# cloud_humidity_sensor.net
KiCad netlist of a schematic drawn in EAGLE
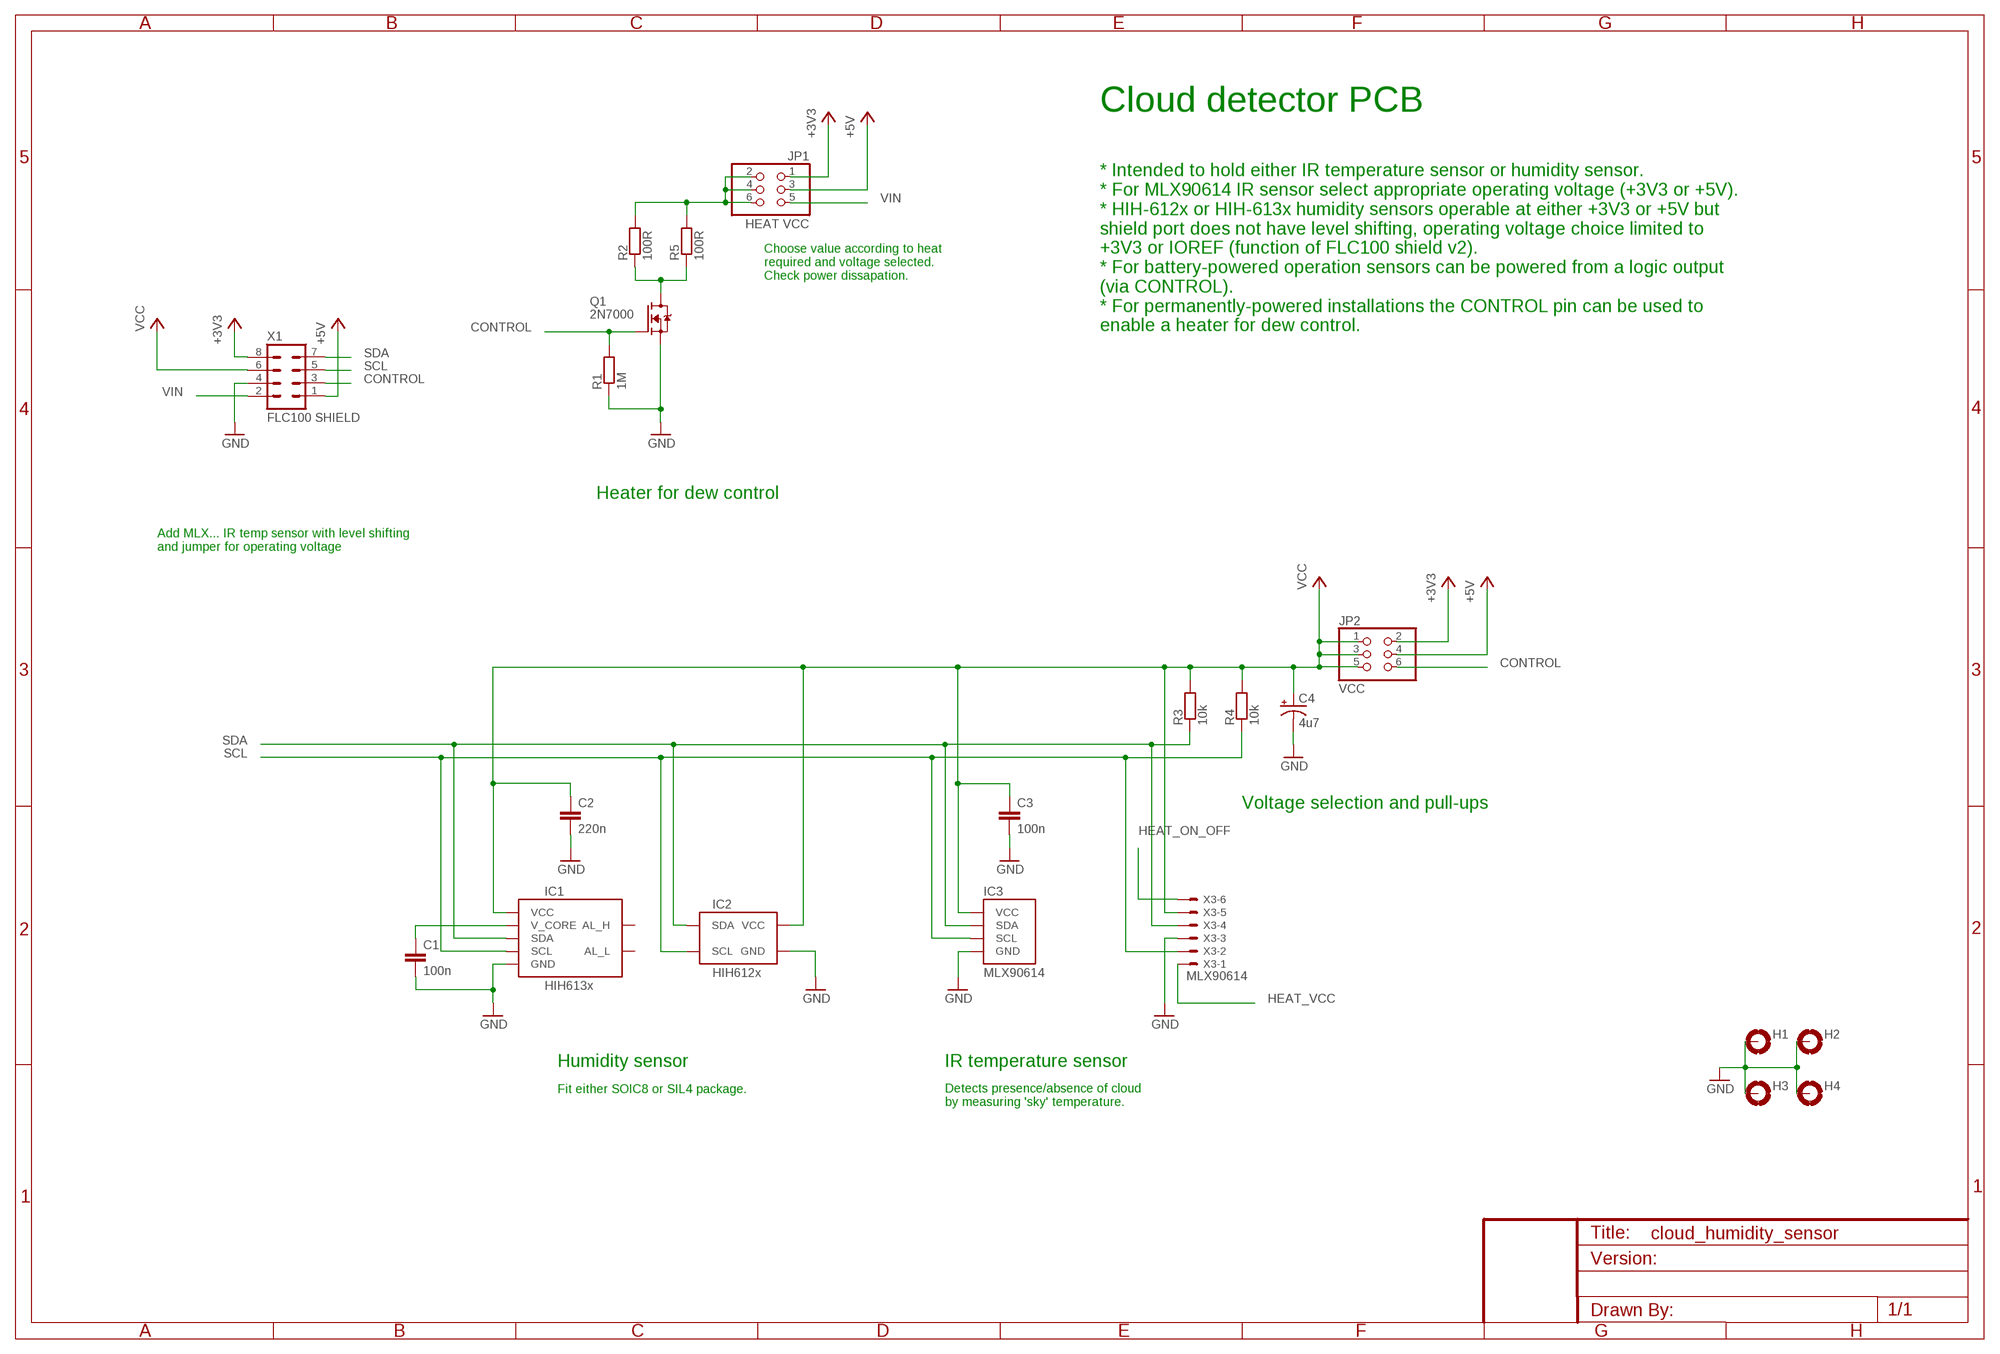
[diagram p0: schematic, sheet 1]

(export (version "E")
  (design (tool "Eeschema 10.0.6"))
  (components
    (comp (ref "C1")
      (value "100n")
      (footprint "eagle-import:CAP-PTH-SMALL")
      (libsource (lib "eagle-import") (part "CAPPTH"))
    )
    (comp (ref "C2")
      (value "220n")
      (footprint "eagle-import:CAP-PTH-SMALL")
      (libsource (lib "eagle-import") (part "CAPPTH"))
    )
    (comp (ref "C3")
      (value "100n")
      (footprint "eagle-import:CAP-PTH-SMALL")
      (libsource (lib "eagle-import") (part "CAPPTH"))
    )
    (comp (ref "C4")
      (value "4u7")
      (footprint "eagle-import:CPOL-RADIAL-10UF-25V")
      (libsource (lib "eagle-import") (part "CAP_POLPTH2"))
    )
    (comp (ref "H1")
      (value "MOUNT-PAD-ROUND3.0")
      (footprint "eagle-import:3,0-PAD")
      (libsource (lib "eagle-import") (part "MOUNT-PAD-ROUND3.0"))
    )
    (comp (ref "H2")
      (value "MOUNT-PAD-ROUND3.0")
      (footprint "eagle-import:3,0-PAD")
      (libsource (lib "eagle-import") (part "MOUNT-PAD-ROUND3.0"))
    )
    (comp (ref "H3")
      (value "MOUNT-PAD-ROUND3.0")
      (footprint "eagle-import:3,0-PAD")
      (libsource (lib "eagle-import") (part "MOUNT-PAD-ROUND3.0"))
    )
    (comp (ref "H4")
      (value "MOUNT-PAD-ROUND3.0")
      (footprint "eagle-import:3,0-PAD")
      (libsource (lib "eagle-import") (part "MOUNT-PAD-ROUND3.0"))
    )
    (comp (ref "IC1")
      (value "HIH613x")
      (footprint "eagle-import:SO08")
      (libsource (lib "eagle-import") (part "HONEYWELL-HIH613XSOIC8"))
    )
    (comp (ref "IC2")
      (value "HIH612x")
      (footprint "eagle-import:SIL04")
      (libsource (lib "eagle-import") (part "HONEYWELL-HIH612X"))
    )
    (comp (ref "IC3")
      (value "MLX90614")
      (footprint "eagle-import:TO39-4")
      (libsource (lib "eagle-import") (part "MLX90614TO-39"))
    )
    (comp (ref "JP1")
      (value "HEAT VCC")
      (footprint "eagle-import:2X03")
      (libsource (lib "eagle-import") (part "PINHD-2X3"))
    )
    (comp (ref "JP2")
      (value "VCC")
      (footprint "eagle-import:2X03")
      (libsource (lib "eagle-import") (part "PINHD-2X3"))
    )
    (comp (ref "Q1")
      (value "2N7000")
      (footprint "eagle-import:TO-92")
      (libsource (lib "eagle-import") (part "2N7000"))
    )
    (comp (ref "R1")
      (value "1M")
      (footprint "eagle-import:RES-AXIAL-0.4")
      (libsource (lib "eagle-import") (part "RESISTOR"))
    )
    (comp (ref "R2")
      (value "100R")
      (footprint "eagle-import:RES-AXIAL-0.4")
      (libsource (lib "eagle-import") (part "RESISTOR"))
    )
    (comp (ref "R3")
      (value "10k")
      (footprint "eagle-import:RES-AXIAL-0.4")
      (libsource (lib "eagle-import") (part "RESISTOR"))
    )
    (comp (ref "R4")
      (value "10k")
      (footprint "eagle-import:RES-AXIAL-0.4")
      (libsource (lib "eagle-import") (part "RESISTOR"))
    )
    (comp (ref "R5")
      (value "100R")
      (footprint "eagle-import:RES-AXIAL-0.4")
      (libsource (lib "eagle-import") (part "RESISTOR"))
    )
    (comp (ref "X1")
      (value "FLC100 SHIELD")
      (footprint "eagle-import:ML8")
      (libsource (lib "eagle-import") (part "ML8"))
    )
    (comp (ref "X3")
      (value "MLX90614")
      (footprint "eagle-import:22-23-2061")
      (fields (field (name "MF") "MOLEX") (field (name "MPN") "22-23-2061"))
      (libsource (lib "eagle-import") (part "22-23-2061"))
    )
  )
  (nets
    (net (code "1") (name "+3V3") (class "Default")
      (node (ref "JP1") (pin "1") (pinfunction "1_1") (pintype "passive"))
      (node (ref "JP2") (pin "2") (pinfunction "2_2") (pintype "passive"))
      (node (ref "X1") (pin "8") (pinfunction "8_8") (pintype "passive"))
    )
    (net (code "2") (name "+5V") (class "Default")
      (node (ref "JP1") (pin "3") (pinfunction "3_3") (pintype "passive"))
      (node (ref "JP2") (pin "4") (pinfunction "4_4") (pintype "passive"))
      (node (ref "X1") (pin "1") (pinfunction "1_1") (pintype "passive"))
    )
    (net (code "3") (name "/CONTROL") (class "Default")
      (node (ref "JP2") (pin "6") (pinfunction "6_6") (pintype "passive"))
      (node (ref "Q1") (pin "2") (pinfunction "G_2") (pintype "passive"))
      (node (ref "R1") (pin "P$2") (pinfunction "2_P$2") (pintype "passive"))
      (node (ref "X1") (pin "3") (pinfunction "3_3") (pintype "passive"))
    )
    (net (code "4") (name "/HEAT_ON_OFF") (class "Default")
      (node (ref "Q1") (pin "3") (pinfunction "D_3") (pintype "passive"))
      (node (ref "R2") (pin "P$1") (pinfunction "1_P$1") (pintype "passive"))
      (node (ref "R5") (pin "P$1") (pinfunction "1_P$1") (pintype "passive"))
      (node (ref "X3") (pin "6") (pinfunction "S_6") (pintype "passive"))
    )
    (net (code "5") (name "/HEAT_VCC") (class "Default")
      (node (ref "JP1") (pin "2") (pinfunction "2_2") (pintype "passive"))
      (node (ref "JP1") (pin "4") (pinfunction "4_4") (pintype "passive"))
      (node (ref "JP1") (pin "6") (pinfunction "6_6") (pintype "passive"))
      (node (ref "R2") (pin "P$2") (pinfunction "2_P$2") (pintype "passive"))
      (node (ref "R5") (pin "P$2") (pinfunction "2_P$2") (pintype "passive"))
      (node (ref "X3") (pin "1") (pinfunction "S_1") (pintype "passive"))
    )
    (net (code "6") (name "/SCL") (class "Default")
      (node (ref "IC1") (pin "3") (pinfunction "SCL_3") (pintype "bidirectional"))
      (node (ref "IC2") (pin "3") (pinfunction "SCL_3") (pintype "bidirectional"))
      (node (ref "IC3") (pin "1") (pinfunction "SCL_1") (pintype "bidirectional"))
      (node (ref "R4") (pin "P$1") (pinfunction "1_P$1") (pintype "passive"))
      (node (ref "X1") (pin "5") (pinfunction "5_5") (pintype "passive"))
      (node (ref "X3") (pin "2") (pinfunction "S_2") (pintype "passive"))
    )
    (net (code "7") (name "/SDA") (class "Default")
      (node (ref "IC1") (pin "4") (pinfunction "SDA_4") (pintype "bidirectional"))
      (node (ref "IC2") (pin "4") (pinfunction "SDA_4") (pintype "bidirectional"))
      (node (ref "IC3") (pin "2") (pinfunction "SDA_2") (pintype "bidirectional"))
      (node (ref "R3") (pin "P$1") (pinfunction "1_P$1") (pintype "passive"))
      (node (ref "X1") (pin "7") (pinfunction "7_7") (pintype "passive"))
      (node (ref "X3") (pin "4") (pinfunction "S_4") (pintype "passive"))
    )
    (net (code "8") (name "/VIN") (class "Default")
      (node (ref "JP1") (pin "5") (pinfunction "5_5") (pintype "passive"))
      (node (ref "X1") (pin "2") (pinfunction "2_2") (pintype "passive"))
    )
    (net (code "9") (name "GND") (class "Default")
      (node (ref "C1") (pin "2") (pinfunction "2_2") (pintype "passive"))
      (node (ref "C2") (pin "2") (pinfunction "2_2") (pintype "passive"))
      (node (ref "C3") (pin "2") (pinfunction "2_2") (pintype "passive"))
      (node (ref "C4") (pin "2") (pinfunction "-_2") (pintype "passive"))
      (node (ref "H1") (pin "B3,0") (pinfunction "MOUNT_B3,0") (pintype "passive"))
      (node (ref "H2") (pin "B3,0") (pinfunction "MOUNT_B3,0") (pintype "passive"))
      (node (ref "H3") (pin "B3,0") (pinfunction "MOUNT_B3,0") (pintype "passive"))
      (node (ref "H4") (pin "B3,0") (pinfunction "MOUNT_B3,0") (pintype "passive"))
      (node (ref "IC1") (pin "2") (pinfunction "GND_2") (pintype "power_in"))
      (node (ref "IC2") (pin "2") (pinfunction "GND_2") (pintype "power_in"))
      (node (ref "IC3") (pin "4") (pinfunction "GND_4") (pintype "power_in"))
      (node (ref "Q1") (pin "1") (pinfunction "S_1") (pintype "passive"))
      (node (ref "R1") (pin "P$1") (pinfunction "1_P$1") (pintype "passive"))
      (node (ref "X1") (pin "4") (pinfunction "4_4") (pintype "passive"))
      (node (ref "X3") (pin "3") (pinfunction "S_3") (pintype "passive"))
    )
    (net (code "10") (name "Net-(IC1-V_CORE)") (class "Default")
      (node (ref "C1") (pin "1") (pinfunction "1_1") (pintype "passive"))
      (node (ref "IC1") (pin "1") (pinfunction "V_CORE_1") (pintype "output"))
    )
    (net (code "11") (name "VCC") (class "Default")
      (node (ref "C2") (pin "1") (pinfunction "1_1") (pintype "passive"))
      (node (ref "C3") (pin "1") (pinfunction "1_1") (pintype "passive"))
      (node (ref "C4") (pin "1") (pinfunction "+_1") (pintype "passive"))
      (node (ref "IC1") (pin "8") (pinfunction "VCC_8") (pintype "power_in"))
      (node (ref "IC2") (pin "1") (pinfunction "VCC_1") (pintype "power_in"))
      (node (ref "IC3") (pin "3") (pinfunction "VCC_3") (pintype "power_in"))
      (node (ref "JP2") (pin "1") (pinfunction "1_1") (pintype "passive"))
      (node (ref "JP2") (pin "3") (pinfunction "3_3") (pintype "passive"))
      (node (ref "JP2") (pin "5") (pinfunction "5_5") (pintype "passive"))
      (node (ref "R3") (pin "P$2") (pinfunction "2_P$2") (pintype "passive"))
      (node (ref "R4") (pin "P$2") (pinfunction "2_P$2") (pintype "passive"))
      (node (ref "X1") (pin "6") (pinfunction "6_6") (pintype "passive"))
      (node (ref "X3") (pin "5") (pinfunction "S_5") (pintype "passive"))
    )
    (net (code "12") (name "unconnected-(IC1-AL_H-Pad5)") (class "Default")
      (node (ref "IC1") (pin "5") (pinfunction "AL_H_5") (pintype "bidirectional"))
    )
    (net (code "13") (name "unconnected-(IC1-AL_L-Pad6)") (class "Default")
      (node (ref "IC1") (pin "6") (pinfunction "AL_L_6") (pintype "bidirectional"))
    )
  )
)
